# CPUBoard_p1.net
KiCad netlist of a schematic drawn in Altium Designer
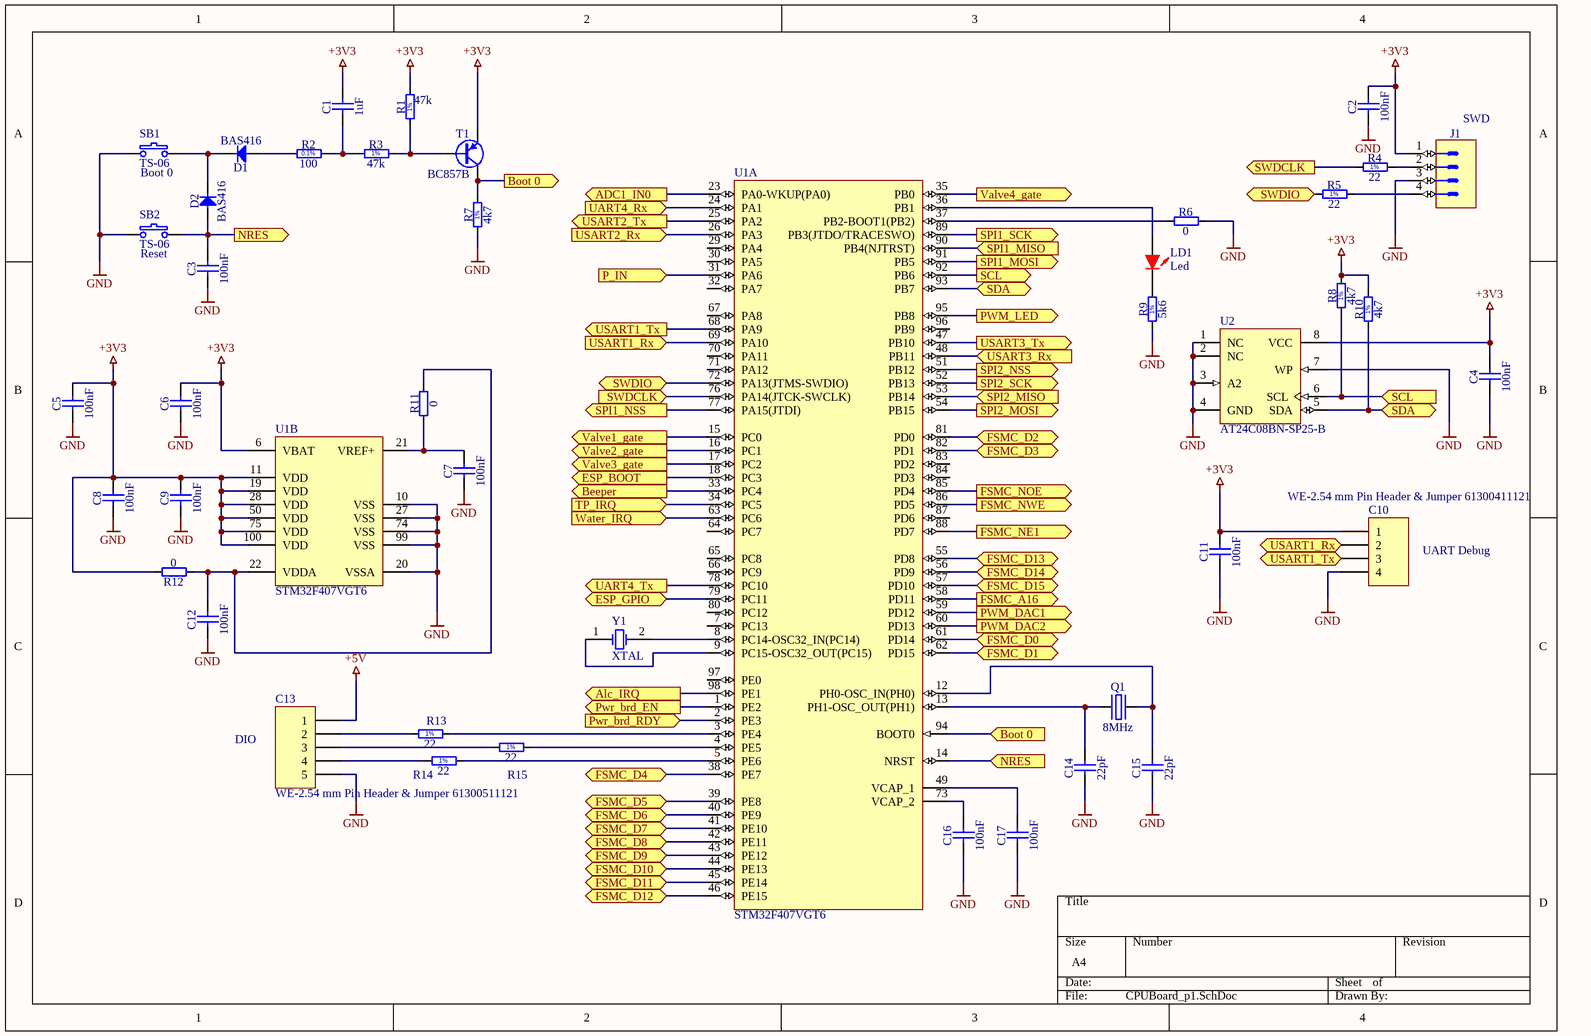
[diagram p0: CPUBoard_p1.SchDoc]

(export (version "E")
  (design (tool "Eeschema 10.0.6"))
  (components
    (comp (ref "C1")
      (value "1uF")
      (footprint "CAPC2012X140N")
      (description "Non-polarised capacitor")
      (fields
        (field (name "PART NUMBER") "CC0805_1UF_35V_20%_X7R")
        (field (name "VOLTAGE") "35V")
        (field (name "AUTHOR") "CERN DEM JLC")
      )
      (libsource (lib "Capacitors") (part "Capacitor - non polarized"))
    )
    (comp (ref "C2")
      (value "100nF")
      (footprint "CAPC2012X135N")
      (description "Non-polarised capacitor")
      (fields
        (field (name "PART NUMBER") "CC0805_100NF_50V_10%_X7R")
        (field (name "VOLTAGE") "50V")
        (field (name "AUTHOR") "CERN DEM JLC")
      )
      (libsource (lib "Capacitors") (part "Capacitor - non polarized"))
    )
    (comp (ref "C3")
      (value "100nF")
      (footprint "CAPC2012X135N")
      (description "Non-polarised capacitor")
      (fields
        (field (name "PART NUMBER") "CC0805_100NF_50V_10%_X7R")
        (field (name "VOLTAGE") "50V")
        (field (name "AUTHOR") "CERN DEM JLC")
      )
      (libsource (lib "Capacitors") (part "Capacitor - non polarized"))
    )
    (comp (ref "C4")
      (value "100nF")
      (footprint "CAPC2012X135N")
      (description "Non-polarised capacitor")
      (fields
        (field (name "PART NUMBER") "CC0805_100NF_50V_10%_X7R")
        (field (name "VOLTAGE") "50V")
        (field (name "AUTHOR") "CERN DEM JLC")
      )
      (libsource (lib "Capacitors") (part "Capacitor - non polarized"))
    )
    (comp (ref "C5")
      (value "100nF")
      (footprint "CAPC2012X135N")
      (description "Non-polarised capacitor")
      (fields
        (field (name "PART NUMBER") "CC0805_100NF_50V_10%_X7R")
        (field (name "VOLTAGE") "50V")
        (field (name "AUTHOR") "CERN DEM JLC")
      )
      (libsource (lib "Capacitors") (part "Capacitor - non polarized"))
    )
    (comp (ref "C6")
      (value "100nF")
      (footprint "CAPC2012X135N")
      (description "Non-polarised capacitor")
      (fields
        (field (name "PART NUMBER") "CC0805_100NF_50V_10%_X7R")
        (field (name "VOLTAGE") "50V")
        (field (name "AUTHOR") "CERN DEM JLC")
      )
      (libsource (lib "Capacitors") (part "Capacitor - non polarized"))
    )
    (comp (ref "C7")
      (value "100nF")
      (footprint "CAPC2012X135N")
      (description "Non-polarised capacitor")
      (fields
        (field (name "PART NUMBER") "CC0805_100NF_50V_10%_X7R")
        (field (name "VOLTAGE") "50V")
        (field (name "AUTHOR") "CERN DEM JLC")
      )
      (libsource (lib "Capacitors") (part "Capacitor - non polarized"))
    )
    (comp (ref "C8")
      (value "100nF")
      (footprint "CAPC2012X135N")
      (description "Non-polarised capacitor")
      (fields
        (field (name "PART NUMBER") "CC0805_100NF_50V_10%_X7R")
        (field (name "VOLTAGE") "50V")
        (field (name "AUTHOR") "CERN DEM JLC")
      )
      (libsource (lib "Capacitors") (part "Capacitor - non polarized"))
    )
    (comp (ref "C9")
      (value "100nF")
      (footprint "CAPC2012X135N")
      (description "Non-polarised capacitor")
      (fields
        (field (name "PART NUMBER") "CC0805_100NF_50V_10%_X7R")
        (field (name "VOLTAGE") "50V")
        (field (name "AUTHOR") "CERN DEM JLC")
      )
      (libsource (lib "Capacitors") (part "Capacitor - non polarized"))
    )
    (comp (ref "C10")
      (value "WE-2.54 mm Pin Header & Jumper 61300411121")
      (footprint "61300411121")
      (description "WR-PHD 2.54mm Pin Header")
      (fields
        (field (name "MANUFACTURER") "WЁ№rth Elektronik eiSos GmbH")
        (field (name "PARTNO") "61300411121")
        (field (name "CREATED BY") "Karrer Zheng")
      )
      (libsource (lib "WE_WR-PHD_Pin Header_2.54mm_rev15c") (part "WE-2.54 mm Pin Header & Jumper 61300411121"))
    )
    (comp (ref "C11")
      (value "100nF")
      (footprint "CAPC2012X135N")
      (description "Non-polarised capacitor")
      (fields
        (field (name "PART NUMBER") "CC0805_100NF_50V_10%_X7R")
        (field (name "VOLTAGE") "50V")
        (field (name "AUTHOR") "CERN DEM JLC")
      )
      (libsource (lib "Capacitors") (part "Capacitor - non polarized"))
    )
    (comp (ref "C12")
      (value "100nF")
      (footprint "CAPC2012X135N")
      (description "Non-polarised capacitor")
      (fields
        (field (name "PART NUMBER") "CC0805_100NF_50V_10%_X7R")
        (field (name "VOLTAGE") "50V")
        (field (name "AUTHOR") "CERN DEM JLC")
      )
      (libsource (lib "Capacitors") (part "Capacitor - non polarized"))
    )
    (comp (ref "C13")
      (value "WE-2.54 mm Pin Header & Jumper 61300511121")
      (footprint "61300511121")
      (description "WR-PHD 2.54mm Pin Header")
      (fields
        (field (name "MANUFACTURER") "WЁ№rth Elektronik eiSos GmbH")
        (field (name "PARTNO") "61300511121")
        (field (name "CREATED BY") "Karrer Zheng")
      )
      (libsource (lib "WE_WR-PHD_Pin Header_2.54mm_rev15c") (part "WE-2.54 mm Pin Header & Jumper 61300511121"))
    )
    (comp (ref "C14")
      (value "22pF")
      (footprint "CAPC2012X135N")
      (description "Non-polarised capacitor")
      (fields
        (field (name "PART NUMBER") "CC0805_22PF_50V_5%_NP0")
        (field (name "VOLTAGE") "50V")
        (field (name "AUTHOR") "CERN DEM JLC")
      )
      (libsource (lib "Capacitors") (part "Capacitor - non polarized"))
    )
    (comp (ref "C15")
      (value "22pF")
      (footprint "CAPC2012X135N")
      (description "Non-polarised capacitor")
      (fields
        (field (name "PART NUMBER") "CC0805_22PF_50V_5%_NP0")
        (field (name "VOLTAGE") "50V")
        (field (name "AUTHOR") "CERN DEM JLC")
      )
      (libsource (lib "Capacitors") (part "Capacitor - non polarized"))
    )
    (comp (ref "C16")
      (value "100nF")
      (footprint "CAPC2012X135N")
      (description "Non-polarised capacitor")
      (fields
        (field (name "PART NUMBER") "CC0805_100NF_50V_10%_X7R")
        (field (name "VOLTAGE") "50V")
        (field (name "AUTHOR") "CERN DEM JLC")
      )
      (libsource (lib "Capacitors") (part "Capacitor - non polarized"))
    )
    (comp (ref "C17")
      (value "100nF")
      (footprint "CAPC2012X135N")
      (description "Non-polarised capacitor")
      (fields
        (field (name "PART NUMBER") "CC0805_100NF_50V_10%_X7R")
        (field (name "VOLTAGE") "50V")
        (field (name "AUTHOR") "CERN DEM JLC")
      )
      (libsource (lib "Capacitors") (part "Capacitor - non polarized"))
    )
    (comp (ref "D1")
      (value "BAS416")
      (footprint "SOD2512X110N")
      (description "Diode")
      (fields
        (field (name "VOLTAGE") "75V")
        (field (name "POWER") "200mA")
        (field (name "AUTHOR") "CERN DEM JLC")
      )
      (libsource (lib "ICs And Semiconductors") (part "Diode"))
    )
    (comp (ref "D2")
      (value "BAS416")
      (footprint "SOD2512X110N")
      (description "Diode")
      (fields
        (field (name "VOLTAGE") "75V")
        (field (name "POWER") "200mA")
        (field (name "AUTHOR") "CERN DEM JLC")
      )
      (libsource (lib "ICs And Semiconductors") (part "Diode"))
    )
    (comp (ref "J1")
      (value "KK®")
      (footprint "MOLEX_22-27-2041")
      (description "Connector 4 Male")
      (fields
        (field (name "PART NUMBER") "MOLEX_22-27-2041")
        (field (name "MANUFACTURER") "MOLEX")
        (field (name "AUTHOR") "CERN DEM JLC")
      )
      (libsource (lib "Connectors") (part "Connector 4 Male"))
    )
    (comp (ref "LD1")
      (value "Led")
      (footprint "Led 0805-Red")
      (description "Red  627nm 12mcd")
      (libsource (lib "Ind LED-LCD") (part "Led 0805 KP-2012EC"))
    )
    (comp (ref "Q1")
      (value "8MHz")
      (footprint "XTAL_HC-49/U-S")
      (description "Quartz Crystal")
      (fields
        (field (name "PART NUMBER") "XTAL_5MHZ_CITIZEN_HC49US5.000MABJ-UB")
        (field (name "MANUFACTURER") "CITIZEN FINETECH MIYOTA CO")
        (field (name "AUTHOR") "CERN DEM JLC")
      )
      (libsource (lib "ICs And Semiconductors") (part "Quartz Crystal"))
    )
    (comp (ref "R1")
      (value "47k")
      (footprint "RESC2012X60N")
      (description "Resistor - 1%")
      (fields
        (field (name "PART NUMBER") "R0805_47K_1%_0.125W_100PPM")
        (field (name "POWER") "0.125W")
        (field (name "AUTHOR") "CERN DEM JLC")
      )
      (libsource (lib "Resistors") (part "Resistor - 1%"))
    )
    (comp (ref "R2")
      (value "100")
      (footprint "RESC2012X60N")
      (description "Resistor - 0.1%")
      (fields
        (field (name "PART NUMBER") "R0805_100R_0.1%_0.1W_10PPM")
        (field (name "POWER") "0.1W")
        (field (name "AUTHOR") "CERN DEM JLC")
      )
      (libsource (lib "Resistors") (part "Resistor - 0.1%"))
    )
    (comp (ref "R3")
      (value "47k")
      (footprint "RESC2012X60N")
      (description "Resistor - 1%")
      (fields
        (field (name "PART NUMBER") "R0805_47K_1%_0.125W_100PPM")
        (field (name "POWER") "0.125W")
        (field (name "AUTHOR") "CERN DEM JLC")
      )
      (libsource (lib "Resistors") (part "Resistor - 1%"))
    )
    (comp (ref "R4")
      (value "22")
      (footprint "RESC2012X60N")
      (description "Resistor - 1%")
      (fields
        (field (name "PART NUMBER") "R0805_22R_1%_0.125W_100PPM")
        (field (name "POWER") "0.125W")
        (field (name "AUTHOR") "CERN DEM JLC")
      )
      (libsource (lib "Resistors") (part "Resistor - 1%"))
    )
    (comp (ref "R5")
      (value "22")
      (footprint "RESC2012X60N")
      (description "Resistor - 1%")
      (fields
        (field (name "PART NUMBER") "R0805_22R_1%_0.125W_100PPM")
        (field (name "POWER") "0.125W")
        (field (name "AUTHOR") "CERN DEM JLC")
      )
      (libsource (lib "Resistors") (part "Resistor - 1%"))
    )
    (comp (ref "R6")
      (value "0")
      (footprint "RESC2012X60N")
      (description "Resistor")
      (fields
        (field (name "PART NUMBER") "R0805_0R_JUMPER")
        (field (name "MANUFACTURER") "GENERIC")
        (field (name "AUTHOR") "CERN DEM JLC")
      )
      (libsource (lib "Resistors") (part "Resistor"))
    )
    (comp (ref "R7")
      (value "4k7")
      (footprint "RESC2012X60N")
      (description "Resistor - 1%")
      (fields
        (field (name "PART NUMBER") "R0805_4K7_1%_0.125W_100PPM")
        (field (name "POWER") "0.125W")
        (field (name "AUTHOR") "CERN DEM JLC")
      )
      (libsource (lib "Resistors") (part "Resistor - 1%"))
    )
    (comp (ref "R8")
      (value "4k7")
      (footprint "RESC2012X60N")
      (description "Resistor - 1%")
      (fields
        (field (name "PART NUMBER") "R0805_4K7_1%_0.125W_100PPM")
        (field (name "POWER") "0.125W")
        (field (name "AUTHOR") "CERN DEM JLC")
      )
      (libsource (lib "Resistors") (part "Resistor - 1%"))
    )
    (comp (ref "R9")
      (value "5k6")
      (footprint "RESC2012X60N")
      (description "Resistor - 1%")
      (fields
        (field (name "PART NUMBER") "R0805_5K6_1%_0.125W_100PPM")
        (field (name "POWER") "0.125W")
        (field (name "AUTHOR") "CERN DEM JLC")
      )
      (libsource (lib "Resistors") (part "Resistor - 1%"))
    )
    (comp (ref "R10")
      (value "4k7")
      (footprint "RESC2012X60N")
      (description "Resistor - 1%")
      (fields
        (field (name "PART NUMBER") "R0805_4K7_1%_0.125W_100PPM")
        (field (name "POWER") "0.125W")
        (field (name "AUTHOR") "CERN DEM JLC")
      )
      (libsource (lib "Resistors") (part "Resistor - 1%"))
    )
    (comp (ref "R11")
      (value "0")
      (footprint "RESC2012X60N")
      (description "Resistor")
      (fields
        (field (name "PART NUMBER") "R0805_0R_JUMPER")
        (field (name "MANUFACTURER") "GENERIC")
        (field (name "AUTHOR") "CERN DEM JLC")
      )
      (libsource (lib "Resistors") (part "Resistor"))
    )
    (comp (ref "R12")
      (value "0")
      (footprint "RESC2012X60N")
      (description "Resistor")
      (fields
        (field (name "PART NUMBER") "R0805_0R_JUMPER")
        (field (name "MANUFACTURER") "GENERIC")
        (field (name "AUTHOR") "CERN DEM JLC")
      )
      (libsource (lib "Resistors") (part "Resistor"))
    )
    (comp (ref "R13")
      (value "22")
      (footprint "RESC2012X60N")
      (description "Resistor - 1%")
      (fields
        (field (name "PART NUMBER") "R0805_22R_1%_0.125W_100PPM")
        (field (name "POWER") "0.125W")
        (field (name "AUTHOR") "CERN DEM JLC")
      )
      (libsource (lib "Resistors") (part "Resistor - 1%"))
    )
    (comp (ref "R14")
      (value "22")
      (footprint "RESC2012X60N")
      (description "Resistor - 1%")
      (fields
        (field (name "PART NUMBER") "R0805_22R_1%_0.125W_100PPM")
        (field (name "POWER") "0.125W")
        (field (name "AUTHOR") "CERN DEM JLC")
      )
      (libsource (lib "Resistors") (part "Resistor - 1%"))
    )
    (comp (ref "R15")
      (value "22")
      (footprint "RESC2012X60N")
      (description "Resistor - 1%")
      (fields
        (field (name "PART NUMBER") "R0805_22R_1%_0.125W_100PPM")
        (field (name "POWER") "0.125W")
        (field (name "AUTHOR") "CERN DEM JLC")
      )
      (libsource (lib "Resistors") (part "Resistor - 1%"))
    )
    (comp (ref "SB1") (value "TS-06") (footprint "TS-06") (libsource (lib "Devise") (part "Buton TS-06")))
    (comp (ref "SB2") (value "TS-06") (footprint "TS-06") (libsource (lib "Devise") (part "Buton TS-06")))
    (comp (ref "T1")
      (value "BC857B")
      (footprint "SOT95P230X110-3N")
      (description "PNP Transistor")
      (fields (field (name "MANUFACTURER") "NXP SEMICONDUCTORS") (field (name "AUTHOR") "CERN DEM JLC"))
      (libsource (lib "ICs And Semiconductors") (part "PNP B1 E2 C3"))
    )
    (comp (ref "U1")
      (value "STM32F407VGT6")
      (footprint "STM-LQFP100_N")
      (fields (field (name "MANUFACTURER") "STMicroelectronics"))
      (libsource (lib "STMicroelectronics STM32 F4") (part "STM32F407VGT6"))
    )
    (comp (ref "U2")
      (value "AT24C08BN-SP25-B")
      (footprint "8S1_N")
      (description "8Kbit (1024 x 8), 2-wire Bus Automotive Serial EEPROM with Write Protect, 2.5V, 8-Pin SOIC, Bulk")
      (libsource (lib "Atmel Serial EEPROM") (part "AT24C08BN-SP25-B"))
    )
    (comp (ref "Y1")
      (value "XTAL")
      (footprint "R38")
      (description "Crystal Oscillator")
      (fields (field (name "PUBLISHER") "Altium Limited"))
      (libsource (lib "Miscellaneous Devices") (part "XTAL"))
    )
  )
  (nets
    (net (code "1") (name "+3V3") (class "Default")
      (node (ref "C1") (pin "2") (pinfunction "2_2") (pintype "passive"))
      (node (ref "C10") (pin "1") (pinfunction "1_1") (pintype "passive"))
      (node (ref "C11") (pin "2") (pinfunction "2_2") (pintype "passive"))
      (node (ref "C2") (pin "2") (pinfunction "2_2") (pintype "passive"))
      (node (ref "C4") (pin "2") (pinfunction "2_2") (pintype "passive"))
      (node (ref "C5") (pin "2") (pinfunction "2_2") (pintype "passive"))
      (node (ref "C6") (pin "2") (pinfunction "2_2") (pintype "passive"))
      (node (ref "C8") (pin "2") (pinfunction "2_2") (pintype "passive"))
      (node (ref "C9") (pin "2") (pinfunction "2_2") (pintype "passive"))
      (node (ref "J1") (pin "1") (pinfunction "1_1") (pintype "bidirectional"))
      (node (ref "R1") (pin "2") (pinfunction "2_2") (pintype "passive"))
      (node (ref "R10") (pin "2") (pinfunction "2_2") (pintype "passive"))
      (node (ref "R12") (pin "2") (pinfunction "2_2") (pintype "passive"))
      (node (ref "R8") (pin "2") (pinfunction "2_2") (pintype "passive"))
      (node (ref "T1") (pin "2") (pinfunction "E_2") (pintype "passive"))
      (node (ref "U1") (pin "100") (pinfunction "VDD_100") (pintype "power_in"))
      (node (ref "U1") (pin "11") (pinfunction "VDD_11") (pintype "power_in"))
      (node (ref "U1") (pin "19") (pinfunction "VDD_19") (pintype "power_in"))
      (node (ref "U1") (pin "28") (pinfunction "VDD_28") (pintype "power_in"))
      (node (ref "U1") (pin "50") (pinfunction "VDD_50") (pintype "power_in"))
      (node (ref "U1") (pin "6") (pinfunction "VBAT_6") (pintype "power_in"))
      (node (ref "U1") (pin "75") (pinfunction "VDD_75") (pintype "power_in"))
      (node (ref "U2") (pin "8") (pinfunction "VCC_8") (pintype "power_in"))
    )
    (net (code "2") (name "+5V") (class "Default")
      (node (ref "C13") (pin "1") (pinfunction "1_1") (pintype "passive"))
    )
    (net (code "3") (name "/ADC1_IN0") (class "Default")
      (node (ref "U1") (pin "23") (pinfunction "PA0-WKUP(PA0)_23") (pintype "bidirectional"))
    )
    (net (code "4") (name "/Alc_IRQ") (class "Default")
      (node (ref "U1") (pin "98") (pinfunction "PE1_98") (pintype "bidirectional"))
    )
    (net (code "5") (name "/Beeper") (class "Default")
      (node (ref "U1") (pin "33") (pinfunction "PC4_33") (pintype "bidirectional"))
    )
    (net (code "6") (name "/Boot 0") (class "Default")
      (node (ref "R7") (pin "2") (pinfunction "2_2") (pintype "passive"))
      (node (ref "T1") (pin "3") (pinfunction "C_3") (pintype "passive"))
      (node (ref "U1") (pin "94") (pinfunction "BOOT0_94") (pintype "input"))
    )
    (net (code "7") (name "/ESP_BOOT") (class "Default")
      (node (ref "U1") (pin "18") (pinfunction "PC3_18") (pintype "bidirectional"))
    )
    (net (code "8") (name "/ESP_GPIO") (class "Default")
      (node (ref "U1") (pin "79") (pinfunction "PC11_79") (pintype "bidirectional"))
    )
    (net (code "9") (name "/FSMC_A16") (class "Default")
      (node (ref "U1") (pin "58") (pinfunction "PD11_58") (pintype "bidirectional"))
    )
    (net (code "10") (name "/FSMC_D0") (class "Default")
      (node (ref "U1") (pin "61") (pinfunction "PD14_61") (pintype "bidirectional"))
    )
    (net (code "11") (name "/FSMC_D1") (class "Default")
      (node (ref "U1") (pin "62") (pinfunction "PD15_62") (pintype "bidirectional"))
    )
    (net (code "12") (name "/FSMC_D2") (class "Default")
      (node (ref "U1") (pin "81") (pinfunction "PD0_81") (pintype "bidirectional"))
    )
    (net (code "13") (name "/FSMC_D3") (class "Default")
      (node (ref "U1") (pin "82") (pinfunction "PD1_82") (pintype "bidirectional"))
    )
    (net (code "14") (name "/FSMC_D4") (class "Default")
      (node (ref "U1") (pin "38") (pinfunction "PE7_38") (pintype "bidirectional"))
    )
    (net (code "15") (name "/FSMC_D5") (class "Default")
      (node (ref "U1") (pin "39") (pinfunction "PE8_39") (pintype "bidirectional"))
    )
    (net (code "16") (name "/FSMC_D6") (class "Default")
      (node (ref "U1") (pin "40") (pinfunction "PE9_40") (pintype "bidirectional"))
    )
    (net (code "17") (name "/FSMC_D7") (class "Default")
      (node (ref "U1") (pin "41") (pinfunction "PE10_41") (pintype "bidirectional"))
    )
    (net (code "18") (name "/FSMC_D8") (class "Default")
      (node (ref "U1") (pin "42") (pinfunction "PE11_42") (pintype "bidirectional"))
    )
    (net (code "19") (name "/FSMC_D9") (class "Default")
      (node (ref "U1") (pin "43") (pinfunction "PE12_43") (pintype "bidirectional"))
    )
    (net (code "20") (name "/FSMC_D10") (class "Default")
      (node (ref "U1") (pin "44") (pinfunction "PE13_44") (pintype "bidirectional"))
    )
    (net (code "21") (name "/FSMC_D11") (class "Default")
      (node (ref "U1") (pin "45") (pinfunction "PE14_45") (pintype "bidirectional"))
    )
    (net (code "22") (name "/FSMC_D12") (class "Default")
      (node (ref "U1") (pin "46") (pinfunction "PE15_46") (pintype "bidirectional"))
    )
    (net (code "23") (name "/FSMC_D13") (class "Default")
      (node (ref "U1") (pin "55") (pinfunction "PD8_55") (pintype "bidirectional"))
    )
    (net (code "24") (name "/FSMC_D14") (class "Default")
      (node (ref "U1") (pin "56") (pinfunction "PD9_56") (pintype "bidirectional"))
    )
    (net (code "25") (name "/FSMC_D15") (class "Default")
      (node (ref "U1") (pin "57") (pinfunction "PD10_57") (pintype "bidirectional"))
    )
    (net (code "26") (name "/FSMC_NE1") (class "Default")
      (node (ref "U1") (pin "88") (pinfunction "PD7_88") (pintype "bidirectional"))
    )
    (net (code "27") (name "/FSMC_NOE") (class "Default")
      (node (ref "U1") (pin "85") (pinfunction "PD4_85") (pintype "bidirectional"))
    )
    (net (code "28") (name "/FSMC_NWE") (class "Default")
      (node (ref "U1") (pin "86") (pinfunction "PD5_86") (pintype "bidirectional"))
    )
    (net (code "29") (name "/NRES") (class "Default")
      (node (ref "C3") (pin "2") (pinfunction "2_2") (pintype "passive"))
      (node (ref "D2") (pin "2") (pinfunction "A_2") (pintype "passive"))
      (node (ref "SB2") (pin "2") (pinfunction "2_2") (pintype "passive"))
      (node (ref "U1") (pin "14") (pinfunction "NRST_14") (pintype "bidirectional"))
    )
    (net (code "30") (name "/PWM_DAC1") (class "Default")
      (node (ref "U1") (pin "59") (pinfunction "PD12_59") (pintype "bidirectional"))
    )
    (net (code "31") (name "/PWM_DAC2") (class "Default")
      (node (ref "U1") (pin "60") (pinfunction "PD13_60") (pintype "bidirectional"))
    )
    (net (code "32") (name "/PWM_LED") (class "Default")
      (node (ref "U1") (pin "95") (pinfunction "PB8_95") (pintype "bidirectional"))
    )
    (net (code "33") (name "/P_IN") (class "Default")
      (node (ref "U1") (pin "31") (pinfunction "PA6_31") (pintype "bidirectional"))
    )
    (net (code "34") (name "/Pwr_brd_EN") (class "Default")
      (node (ref "U1") (pin "1") (pinfunction "PE2_1") (pintype "bidirectional"))
    )
    (net (code "35") (name "/Pwr_brd_RDY") (class "Default")
      (node (ref "U1") (pin "2") (pinfunction "PE3_2") (pintype "bidirectional"))
    )
    (net (code "36") (name "/SCL") (class "Default")
      (node (ref "R8") (pin "1") (pinfunction "1_1") (pintype "passive"))
      (node (ref "U1") (pin "92") (pinfunction "PB6_92") (pintype "bidirectional"))
      (node (ref "U2") (pin "6") (pinfunction "SCL_6") (pintype "input"))
    )
    (net (code "37") (name "/SDA") (class "Default")
      (node (ref "R10") (pin "1") (pinfunction "1_1") (pintype "passive"))
      (node (ref "U1") (pin "93") (pinfunction "PB7_93") (pintype "bidirectional"))
      (node (ref "U2") (pin "5") (pinfunction "SDA_5") (pintype "bidirectional"))
    )
    (net (code "38") (name "/SPI1_MISO") (class "Default")
      (node (ref "U1") (pin "90") (pinfunction "PB4(NJTRST)_90") (pintype "bidirectional"))
    )
    (net (code "39") (name "/SPI1_MOSI") (class "Default")
      (node (ref "U1") (pin "91") (pinfunction "PB5_91") (pintype "bidirectional"))
    )
    (net (code "40") (name "/SPI1_NSS") (class "Default")
      (node (ref "U1") (pin "77") (pinfunction "PA15(JTDI)_77") (pintype "bidirectional"))
    )
    (net (code "41") (name "/SPI1_SCK") (class "Default")
      (node (ref "U1") (pin "89") (pinfunction "PB3(JTDO/TRACESWO)_89") (pintype "bidirectional"))
    )
    (net (code "42") (name "/SPI2_MISO") (class "Default")
      (node (ref "U1") (pin "53") (pinfunction "PB14_53") (pintype "bidirectional"))
    )
    (net (code "43") (name "/SPI2_MOSI") (class "Default")
      (node (ref "U1") (pin "54") (pinfunction "PB15_54") (pintype "bidirectional"))
    )
    (net (code "44") (name "/SPI2_NSS") (class "Default")
      (node (ref "U1") (pin "51") (pinfunction "PB12_51") (pintype "bidirectional"))
    )
    (net (code "45") (name "/SPI2_SCK") (class "Default")
      (node (ref "U1") (pin "52") (pinfunction "PB13_52") (pintype "bidirectional"))
    )
    (net (code "46") (name "/SWDCLK") (class "Default")
      (node (ref "R4") (pin "1") (pinfunction "1_1") (pintype "passive"))
      (node (ref "U1") (pin "76") (pinfunction "PA14(JTCK-SWCLK)_76") (pintype "bidirectional"))
    )
    (net (code "47") (name "/SWDIO") (class "Default")
      (node (ref "R5") (pin "1") (pinfunction "1_1") (pintype "passive"))
      (node (ref "U1") (pin "72") (pinfunction "PA13(JTMS-SWDIO)_72") (pintype "bidirectional"))
    )
    (net (code "48") (name "/TP_IRQ") (class "Default")
      (node (ref "U1") (pin "34") (pinfunction "PC5_34") (pintype "bidirectional"))
    )
    (net (code "49") (name "/UART4_Rx") (class "Default")
      (node (ref "U1") (pin "24") (pinfunction "PA1_24") (pintype "bidirectional"))
    )
    (net (code "50") (name "/UART4_Tx") (class "Default")
      (node (ref "U1") (pin "78") (pinfunction "PC10_78") (pintype "bidirectional"))
    )
    (net (code "51") (name "/USART1_Rx") (class "Default")
      (node (ref "C10") (pin "2") (pinfunction "2_2") (pintype "passive"))
      (node (ref "U1") (pin "69") (pinfunction "PA10_69") (pintype "bidirectional"))
    )
    (net (code "52") (name "/USART1_Tx") (class "Default")
      (node (ref "C10") (pin "3") (pinfunction "3_3") (pintype "passive"))
      (node (ref "U1") (pin "68") (pinfunction "PA9_68") (pintype "bidirectional"))
    )
    (net (code "53") (name "/USART2_Rx") (class "Default")
      (node (ref "U1") (pin "26") (pinfunction "PA3_26") (pintype "bidirectional"))
    )
    (net (code "54") (name "/USART2_Tx") (class "Default")
      (node (ref "U1") (pin "25") (pinfunction "PA2_25") (pintype "bidirectional"))
    )
    (net (code "55") (name "/USART3_Rx") (class "Default")
      (node (ref "U1") (pin "48") (pinfunction "PB11_48") (pintype "bidirectional"))
    )
    (net (code "56") (name "/USART3_Tx") (class "Default")
      (node (ref "U1") (pin "47") (pinfunction "PB10_47") (pintype "bidirectional"))
    )
    (net (code "57") (name "/Valve1_gate") (class "Default")
      (node (ref "U1") (pin "15") (pinfunction "PC0_15") (pintype "bidirectional"))
    )
    (net (code "58") (name "/Valve2_gate") (class "Default")
      (node (ref "U1") (pin "16") (pinfunction "PC1_16") (pintype "bidirectional"))
    )
    (net (code "59") (name "/Valve3_gate") (class "Default")
      (node (ref "U1") (pin "17") (pinfunction "PC2_17") (pintype "bidirectional"))
    )
    (net (code "60") (name "/Valve4_gate") (class "Default")
      (node (ref "U1") (pin "35") (pinfunction "PB0_35") (pintype "bidirectional"))
    )
    (net (code "61") (name "/Water_IRQ") (class "Default")
      (node (ref "U1") (pin "63") (pinfunction "PC6_63") (pintype "bidirectional"))
    )
    (net (code "62") (name "GND") (class "Default")
      (node (ref "C10") (pin "4") (pinfunction "4_4") (pintype "passive"))
      (node (ref "C11") (pin "1") (pinfunction "1_1") (pintype "passive"))
      (node (ref "C12") (pin "1") (pinfunction "1_1") (pintype "passive"))
      (node (ref "C13") (pin "5") (pinfunction "5_5") (pintype "passive"))
      (node (ref "C14") (pin "1") (pinfunction "1_1") (pintype "passive"))
      (node (ref "C15") (pin "1") (pinfunction "1_1") (pintype "passive"))
      (node (ref "C16") (pin "1") (pinfunction "1_1") (pintype "passive"))
      (node (ref "C17") (pin "1") (pinfunction "1_1") (pintype "passive"))
      (node (ref "C2") (pin "1") (pinfunction "1_1") (pintype "passive"))
      (node (ref "C3") (pin "1") (pinfunction "1_1") (pintype "passive"))
      (node (ref "C4") (pin "1") (pinfunction "1_1") (pintype "passive"))
      (node (ref "C5") (pin "1") (pinfunction "1_1") (pintype "passive"))
      (node (ref "C6") (pin "1") (pinfunction "1_1") (pintype "passive"))
      (node (ref "C7") (pin "1") (pinfunction "1_1") (pintype "passive"))
      (node (ref "C8") (pin "1") (pinfunction "1_1") (pintype "passive"))
      (node (ref "C9") (pin "1") (pinfunction "1_1") (pintype "passive"))
      (node (ref "J1") (pin "3") (pinfunction "3_3") (pintype "bidirectional"))
      (node (ref "R6") (pin "2") (pinfunction "2_2") (pintype "passive"))
      (node (ref "R7") (pin "1") (pinfunction "1_1") (pintype "passive"))
      (node (ref "R9") (pin "1") (pinfunction "1_1") (pintype "passive"))
      (node (ref "SB1") (pin "1") (pinfunction "1_1") (pintype "passive"))
      (node (ref "SB2") (pin "1") (pinfunction "1_1") (pintype "passive"))
      (node (ref "U1") (pin "10") (pinfunction "VSS_10") (pintype "power_in"))
      (node (ref "U1") (pin "20") (pinfunction "VSSA_20") (pintype "power_in"))
      (node (ref "U1") (pin "27") (pinfunction "VSS_27") (pintype "power_in"))
      (node (ref "U1") (pin "74") (pinfunction "VSS_74") (pintype "power_in"))
      (node (ref "U1") (pin "99") (pinfunction "VSS_99") (pintype "power_in"))
      (node (ref "U2") (pin "1") (pinfunction "NC_1") (pintype "passive"))
      (node (ref "U2") (pin "2") (pinfunction "NC_2") (pintype "passive"))
      (node (ref "U2") (pin "3") (pinfunction "A2_3") (pintype "input"))
      (node (ref "U2") (pin "4") (pinfunction "GND_4") (pintype "power_in"))
      (node (ref "U2") (pin "7") (pinfunction "WP_7") (pintype "input"))
    )
    (net (code "63") (name "Net-(C1-Pad1)") (class "Default")
      (node (ref "C1") (pin "1") (pinfunction "1_1") (pintype "passive"))
      (node (ref "R2") (pin "2") (pinfunction "2_2") (pintype "passive"))
      (node (ref "R3") (pin "1") (pinfunction "1_1") (pintype "passive"))
    )
    (net (code "64") (name "Net-(C13-Pad2)") (class "Default")
      (node (ref "C13") (pin "2") (pinfunction "2_2") (pintype "passive"))
      (node (ref "R13") (pin "1") (pinfunction "1_1") (pintype "passive"))
    )
    (net (code "65") (name "Net-(C13-Pad3)") (class "Default")
      (node (ref "C13") (pin "3") (pinfunction "3_3") (pintype "passive"))
      (node (ref "R15") (pin "1") (pinfunction "1_1") (pintype "passive"))
    )
    (net (code "66") (name "Net-(C13-Pad4)") (class "Default")
      (node (ref "C13") (pin "4") (pinfunction "4_4") (pintype "passive"))
      (node (ref "R14") (pin "1") (pinfunction "1_1") (pintype "passive"))
    )
    (net (code "67") (name "Net-(D1-A)") (class "Default")
      (node (ref "D1") (pin "2") (pinfunction "A_2") (pintype "passive"))
      (node (ref "R2") (pin "1") (pinfunction "1_1") (pintype "passive"))
    )
    (net (code "68") (name "Net-(D1-C)") (class "Default")
      (node (ref "D1") (pin "1") (pinfunction "C_1") (pintype "passive"))
      (node (ref "D2") (pin "1") (pinfunction "C_1") (pintype "passive"))
      (node (ref "SB1") (pin "2") (pinfunction "2_2") (pintype "passive"))
    )
    (net (code "69") (name "Net-(J1-Pad2)") (class "Default")
      (node (ref "J1") (pin "2") (pinfunction "2_2") (pintype "bidirectional"))
      (node (ref "R4") (pin "2") (pinfunction "2_2") (pintype "passive"))
    )
    (net (code "70") (name "Net-(J1-Pad4)") (class "Default")
      (node (ref "J1") (pin "4") (pinfunction "4_4") (pintype "bidirectional"))
      (node (ref "R5") (pin "2") (pinfunction "2_2") (pintype "passive"))
    )
    (net (code "71") (name "Net-(LD1-A)") (class "Default")
      (node (ref "LD1") (pin "1") (pinfunction "A_1") (pintype "passive"))
      (node (ref "U1") (pin "36") (pinfunction "PB1_36") (pintype "bidirectional"))
    )
    (net (code "72") (name "Net-(LD1-K)") (class "Default")
      (node (ref "LD1") (pin "2") (pinfunction "K_2") (pintype "passive"))
      (node (ref "R9") (pin "2") (pinfunction "2_2") (pintype "passive"))
    )
    (net (code "73") (name "Net-(Q1-OSC1)") (class "Default")
      (node (ref "C14") (pin "2") (pinfunction "2_2") (pintype "passive"))
      (node (ref "Q1") (pin "1") (pinfunction "OSC1_1") (pintype "passive"))
      (node (ref "U1") (pin "13") (pinfunction "PH1-OSC_OUT(PH1)_13") (pintype "bidirectional"))
    )
    (net (code "74") (name "Net-(Q1-OSC2)") (class "Default")
      (node (ref "C15") (pin "2") (pinfunction "2_2") (pintype "passive"))
      (node (ref "Q1") (pin "2") (pinfunction "OSC2_2") (pintype "passive"))
      (node (ref "U1") (pin "12") (pinfunction "PH0-OSC_IN(PH0)_12") (pintype "bidirectional"))
    )
    (net (code "75") (name "Net-(T1-B)") (class "Default")
      (node (ref "R1") (pin "1") (pinfunction "1_1") (pintype "passive"))
      (node (ref "R3") (pin "2") (pinfunction "2_2") (pintype "passive"))
      (node (ref "T1") (pin "1") (pinfunction "B_1") (pintype "passive"))
    )
    (net (code "76") (name "Net-(U1A-PB2-BOOT1(PB2))") (class "Default")
      (node (ref "R6") (pin "1") (pinfunction "1_1") (pintype "passive"))
      (node (ref "U1") (pin "37") (pinfunction "PB2-BOOT1(PB2)_37") (pintype "bidirectional"))
    )
    (net (code "77") (name "Net-(U1A-PC14-OSC32_IN(PC14))") (class "Default")
      (node (ref "U1") (pin "8") (pinfunction "PC14-OSC32_IN(PC14)_8") (pintype "bidirectional"))
      (node (ref "Y1") (pin "2") (pinfunction "OSC2_2") (pintype "passive"))
    )
    (net (code "78") (name "Net-(U1A-PC15-OSC32_OUT(PC15))") (class "Default")
      (node (ref "U1") (pin "9") (pinfunction "PC15-OSC32_OUT(PC15)_9") (pintype "bidirectional"))
      (node (ref "Y1") (pin "1") (pinfunction "OSC1_1") (pintype "passive"))
    )
    (net (code "79") (name "Net-(U1A-PE4)") (class "Default")
      (node (ref "R13") (pin "2") (pinfunction "2_2") (pintype "passive"))
      (node (ref "U1") (pin "3") (pinfunction "PE4_3") (pintype "bidirectional"))
    )
    (net (code "80") (name "Net-(U1A-PE5)") (class "Default")
      (node (ref "R15") (pin "2") (pinfunction "2_2") (pintype "passive"))
      (node (ref "U1") (pin "4") (pinfunction "PE5_4") (pintype "bidirectional"))
    )
    (net (code "81") (name "Net-(U1A-PE6)") (class "Default")
      (node (ref "R14") (pin "2") (pinfunction "2_2") (pintype "passive"))
      (node (ref "U1") (pin "5") (pinfunction "PE6_5") (pintype "bidirectional"))
    )
    (net (code "82") (name "Net-(U1A-VCAP_1)") (class "Default")
      (node (ref "C17") (pin "2") (pinfunction "2_2") (pintype "passive"))
      (node (ref "U1") (pin "49") (pinfunction "VCAP_1_49") (pintype "power_in"))
    )
    (net (code "83") (name "Net-(U1A-VCAP_2)") (class "Default")
      (node (ref "C16") (pin "2") (pinfunction "2_2") (pintype "passive"))
      (node (ref "U1") (pin "73") (pinfunction "VCAP_2_73") (pintype "power_in"))
    )
    (net (code "84") (name "Net-(U1B-VDDA)") (class "Default")
      (node (ref "C12") (pin "2") (pinfunction "2_2") (pintype "passive"))
      (node (ref "R11") (pin "2") (pinfunction "2_2") (pintype "passive"))
      (node (ref "R12") (pin "1") (pinfunction "1_1") (pintype "passive"))
      (node (ref "U1") (pin "22") (pinfunction "VDDA_22") (pintype "power_in"))
    )
    (net (code "85") (name "Net-(U1B-VREF+)") (class "Default")
      (node (ref "C7") (pin "2") (pinfunction "2_2") (pintype "passive"))
      (node (ref "R11") (pin "1") (pinfunction "1_1") (pintype "passive"))
      (node (ref "U1") (pin "21") (pinfunction "VREF+_21") (pintype "power_in"))
    )
    (net (code "86") (name "unconnected-(U1A-PA4-Pad29)") (class "Default")
      (node (ref "U1") (pin "29") (pinfunction "PA4_29") (pintype "bidirectional"))
    )
    (net (code "87") (name "unconnected-(U1A-PA5-Pad30)") (class "Default")
      (node (ref "U1") (pin "30") (pinfunction "PA5_30") (pintype "bidirectional"))
    )
    (net (code "88") (name "unconnected-(U1A-PA7-Pad32)") (class "Default")
      (node (ref "U1") (pin "32") (pinfunction "PA7_32") (pintype "bidirectional"))
    )
    (net (code "89") (name "unconnected-(U1A-PA8-Pad67)") (class "Default")
      (node (ref "U1") (pin "67") (pinfunction "PA8_67") (pintype "bidirectional"))
    )
    (net (code "90") (name "unconnected-(U1A-PA11-Pad70)") (class "Default")
      (node (ref "U1") (pin "70") (pinfunction "PA11_70") (pintype "bidirectional"))
    )
    (net (code "91") (name "unconnected-(U1A-PA12-Pad71)") (class "Default")
      (node (ref "U1") (pin "71") (pinfunction "PA12_71") (pintype "bidirectional"))
    )
    (net (code "92") (name "unconnected-(U1A-PB9-Pad96)") (class "Default")
      (node (ref "U1") (pin "96") (pinfunction "PB9_96") (pintype "bidirectional"))
    )
    (net (code "93") (name "unconnected-(U1A-PC7-Pad64)") (class "Default")
      (node (ref "U1") (pin "64") (pinfunction "PC7_64") (pintype "bidirectional"))
    )
    (net (code "94") (name "unconnected-(U1A-PC8-Pad65)") (class "Default")
      (node (ref "U1") (pin "65") (pinfunction "PC8_65") (pintype "bidirectional"))
    )
    (net (code "95") (name "unconnected-(U1A-PC9-Pad66)") (class "Default")
      (node (ref "U1") (pin "66") (pinfunction "PC9_66") (pintype "bidirectional"))
    )
    (net (code "96") (name "unconnected-(U1A-PC12-Pad80)") (class "Default")
      (node (ref "U1") (pin "80") (pinfunction "PC12_80") (pintype "bidirectional"))
    )
    (net (code "97") (name "unconnected-(U1A-PC13-Pad7)") (class "Default")
      (node (ref "U1") (pin "7") (pinfunction "PC13_7") (pintype "bidirectional"))
    )
    (net (code "98") (name "unconnected-(U1A-PD2-Pad83)") (class "Default")
      (node (ref "U1") (pin "83") (pinfunction "PD2_83") (pintype "bidirectional"))
    )
    (net (code "99") (name "unconnected-(U1A-PD3-Pad84)") (class "Default")
      (node (ref "U1") (pin "84") (pinfunction "PD3_84") (pintype "bidirectional"))
    )
    (net (code "100") (name "unconnected-(U1A-PD6-Pad87)") (class "Default")
      (node (ref "U1") (pin "87") (pinfunction "PD6_87") (pintype "bidirectional"))
    )
    (net (code "101") (name "unconnected-(U1A-PE0-Pad97)") (class "Default")
      (node (ref "U1") (pin "97") (pinfunction "PE0_97") (pintype "bidirectional"))
    )
  )
)
